# ESPcam.net
KiCad netlist of a schematic drawn in EAGLE
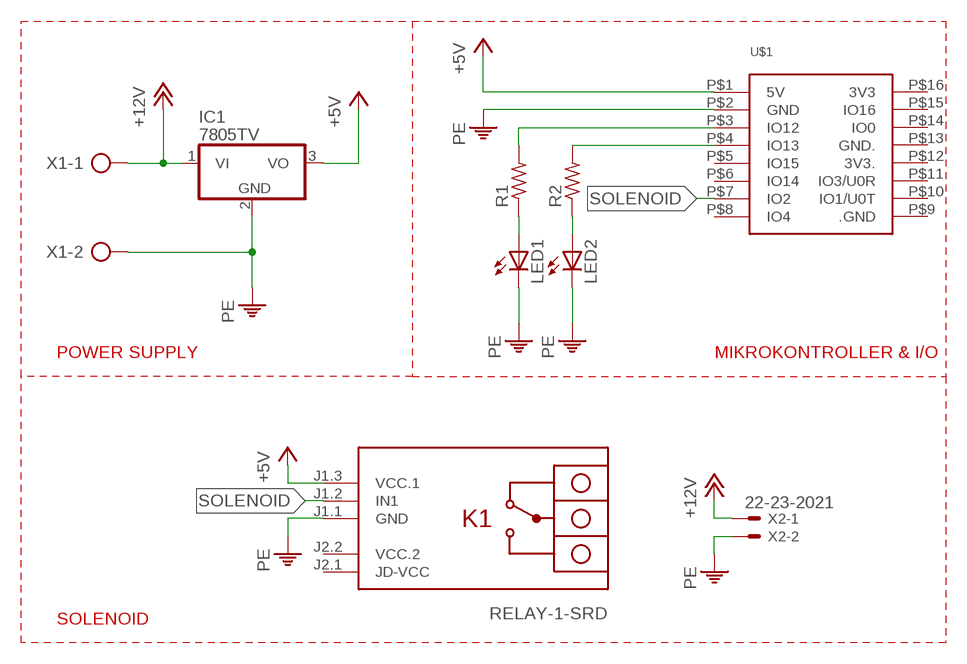
[diagram p0: schematic, sheet 1]

(export (version "E")
  (design (tool "Eeschema 10.0.6"))
  (components
    (comp (ref "IC1")
      (value "7805TV")
      (footprint "eagle-import:TO220V")
      (libsource (lib "eagle-import") (part "78TV05"))
    )
    (comp (ref "LED1")
      (value "LED5MM")
      (footprint "eagle-import:LED5MM")
      (libsource (lib "eagle-import") (part "LED5MM"))
    )
    (comp (ref "LED2")
      (value "LED5MM")
      (footprint "eagle-import:LED5MM")
      (libsource (lib "eagle-import") (part "LED5MM"))
    )
    (comp (ref "R1")
      (value "R-US_0207/15")
      (footprint "eagle-import:0207_15")
      (libsource (lib "eagle-import") (part "R-US_0207/15"))
    )
    (comp (ref "R2")
      (value "R-US_0207/15")
      (footprint "eagle-import:0207_15")
      (libsource (lib "eagle-import") (part "R-US_0207/15"))
    )
    (comp (ref "U$1")
      (value "ESP32-CAM")
      (footprint "eagle-import:ESP32-CAM")
      (fields (field (name "MF") "AI-Thinker"))
      (libsource (lib "eagle-import") (part "ESP32-CAM"))
    )
    (comp (ref "U$2")
      (value "RELAY-1-SRD")
      (footprint "eagle-import:RELAY-1-SRD")
      (libsource (lib "eagle-import") (part "RELAY-1-SRD"))
    )
    (comp (ref "X1")
      (value "AK500/2-H")
      (footprint "eagle-import:AK500_2-H")
      (libsource (lib "eagle-import") (part "AK500/2-H"))
    )
    (comp (ref "X2")
      (value "22-23-2021")
      (footprint "eagle-import:22-23-2021")
      (fields (field (name "MF") "MOLEX"))
      (libsource (lib "eagle-import") (part "22-23-2021"))
    )
  )
  (nets
    (net (code "1") (name "+5V") (class "Default")
      (node (ref "IC1") (pin "3") (pinfunction "VO_3") (pintype "passive"))
      (node (ref "U$1") (pin "P$1") (pinfunction "5V_P$1") (pintype "bidirectional"))
      (node (ref "U$2") (pin "J1.3") (pinfunction "VCC.1_J1.3") (pintype "power_in"))
    )
    (net (code "2") (name "+12V") (class "Default")
      (node (ref "IC1") (pin "1") (pinfunction "VI_1") (pintype "input"))
      (node (ref "X1") (pin "1") (pinfunction "KL_1") (pintype "passive"))
      (node (ref "X2") (pin "1") (pinfunction "S_1") (pintype "passive"))
    )
    (net (code "3") (name "/VCC.2") (class "Default")
      (node (ref "U$2") (pin "J2.2") (pinfunction "VCC.2_J2.2") (pintype "power_in"))
    )
    (net (code "4") (name "Net-(LED1-PadA)") (class "Default")
      (node (ref "LED1") (pin "A") (pinfunction "A_A") (pintype "passive"))
      (node (ref "R1") (pin "1") (pinfunction "1_1") (pintype "passive"))
    )
    (net (code "5") (name "Net-(LED2-PadA)") (class "Default")
      (node (ref "LED2") (pin "A") (pinfunction "A_A") (pintype "passive"))
      (node (ref "R2") (pin "1") (pinfunction "1_1") (pintype "passive"))
    )
    (net (code "6") (name "Net-(U$1-IO12)") (class "Default")
      (node (ref "R1") (pin "2") (pinfunction "2_2") (pintype "passive"))
      (node (ref "U$1") (pin "P$3") (pinfunction "IO12_P$3") (pintype "bidirectional"))
    )
    (net (code "7") (name "Net-(U$1-IO13)") (class "Default")
      (node (ref "R2") (pin "2") (pinfunction "2_2") (pintype "passive"))
      (node (ref "U$1") (pin "P$4") (pinfunction "IO13_P$4") (pintype "bidirectional"))
    )
    (net (code "8") (name "PE") (class "Default")
      (node (ref "IC1") (pin "2") (pinfunction "GND_2") (pintype "passive"))
      (node (ref "LED1") (pin "K") (pinfunction "C_K") (pintype "passive"))
      (node (ref "LED2") (pin "K") (pinfunction "C_K") (pintype "passive"))
      (node (ref "U$1") (pin "P$2") (pinfunction "GND_P$2") (pintype "bidirectional"))
      (node (ref "U$2") (pin "J1.1") (pinfunction "GND_J1.1") (pintype "power_in"))
      (node (ref "X1") (pin "2") (pinfunction "KL_2") (pintype "passive"))
      (node (ref "X2") (pin "2") (pinfunction "S_2") (pintype "passive"))
    )
    (net (code "9") (name "SOLENOID") (class "Default")
      (node (ref "U$1") (pin "P$7") (pinfunction "IO2_P$7") (pintype "bidirectional"))
      (node (ref "U$2") (pin "J1.2") (pinfunction "IN1_J1.2") (pintype "bidirectional"))
    )
    (net (code "10") (name "unconnected-(U$1-.GND-PadP$9)") (class "Default")
      (node (ref "U$1") (pin "P$9") (pinfunction ".GND_P$9") (pintype "bidirectional"))
    )
    (net (code "11") (name "unconnected-(U$1-3V3-PadP$16)") (class "Default")
      (node (ref "U$1") (pin "P$16") (pinfunction "3V3_P$16") (pintype "bidirectional"))
    )
    (net (code "12") (name "unconnected-(U$1-3V3.-PadP$12)") (class "Default")
      (node (ref "U$1") (pin "P$12") (pinfunction "3V3._P$12") (pintype "bidirectional"))
    )
    (net (code "13") (name "unconnected-(U$1-GND.-PadP$13)") (class "Default")
      (node (ref "U$1") (pin "P$13") (pinfunction "GND._P$13") (pintype "bidirectional"))
    )
    (net (code "14") (name "unconnected-(U$1-IO0-PadP$14)") (class "Default")
      (node (ref "U$1") (pin "P$14") (pinfunction "IO0_P$14") (pintype "bidirectional"))
    )
    (net (code "15") (name "unconnected-(U$1-IO1{slash}U0T-PadP$10)") (class "Default")
      (node (ref "U$1") (pin "P$10") (pinfunction "IO1/U0T_P$10") (pintype "bidirectional"))
    )
    (net (code "16") (name "unconnected-(U$1-IO3{slash}U0R-PadP$11)") (class "Default")
      (node (ref "U$1") (pin "P$11") (pinfunction "IO3/U0R_P$11") (pintype "bidirectional"))
    )
    (net (code "17") (name "unconnected-(U$1-IO4-PadP$8)") (class "Default")
      (node (ref "U$1") (pin "P$8") (pinfunction "IO4_P$8") (pintype "bidirectional"))
    )
    (net (code "18") (name "unconnected-(U$1-IO14-PadP$6)") (class "Default")
      (node (ref "U$1") (pin "P$6") (pinfunction "IO14_P$6") (pintype "bidirectional"))
    )
    (net (code "19") (name "unconnected-(U$1-IO15-PadP$5)") (class "Default")
      (node (ref "U$1") (pin "P$5") (pinfunction "IO15_P$5") (pintype "bidirectional"))
    )
    (net (code "20") (name "unconnected-(U$1-IO16-PadP$15)") (class "Default")
      (node (ref "U$1") (pin "P$15") (pinfunction "IO16_P$15") (pintype "bidirectional"))
    )
    (net (code "21") (name "unconnected-(U$2-JD-VCC-PadJ2.1)") (class "Default")
      (node (ref "U$2") (pin "J2.1") (pinfunction "JD-VCC_J2.1") (pintype "bidirectional"))
    )
  )
)
